# 10_RELAY.net
KiCad netlist of a schematic drawn in Altium Designer
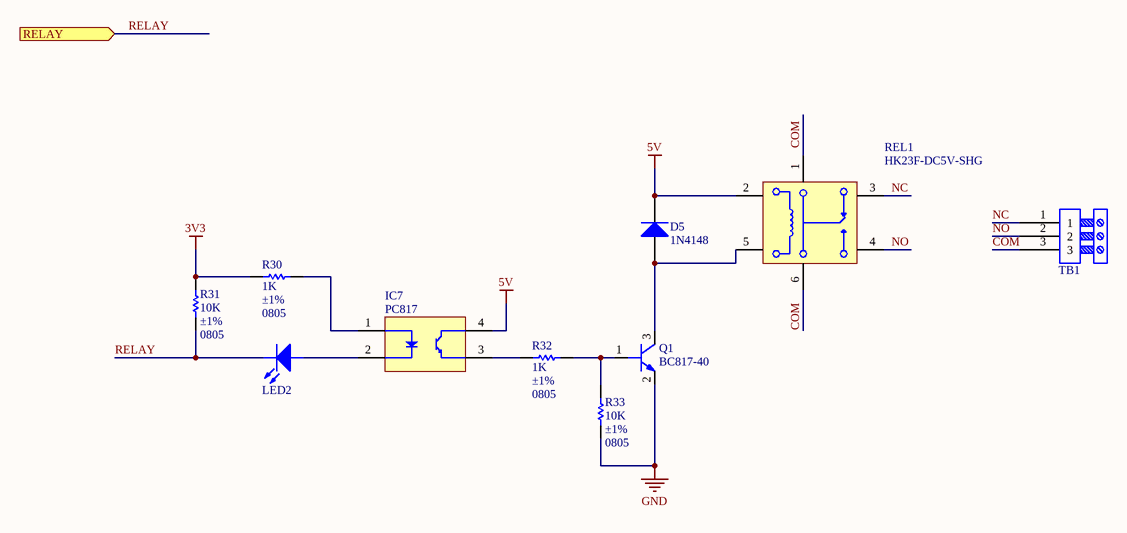
[diagram p0: 10.RELAY.SchDoc]

(export (version "E")
  (design (tool "Eeschema 10.0.6"))
  (components
    (comp (ref "D5")
      (value "1N4148")
      (footprint "SOD323")
      (description "DIODE GEN PURP 75V 150MA SOD323")
      (fields (field (name "PART NUMBER") "SSEM00021") (field (name "VOLTAGE") "75V"))
      (libsource (lib "ComponentDatabase") (part "DIODE"))
    )
    (comp (ref "IC7")
      (value "PC817")
      (footprint "SMD-4")
      (description "OPTOISOLTR 5KV TRANSISTOR 4-SMD")
      (fields
        (field (name "PART NUMBER") "SISO00004")
        (field (name "MANUFACTURER") "Everlight Electronics Co Ltd")
      )
      (libsource (lib "ComponentDatabase") (part "PC817"))
    )
    (comp (ref "LED2")
      (value "LED")
      (footprint "LEDC2012X70N_EIA0805_RED")
      (description "LED SUPER RED CLR THIN 0805 SMD")
      (fields (field (name "PART NUMBER") "SOPT00004") (field (name "MANUFACTURER") "Lite-On Inc"))
      (libsource (lib "ComponentDatabase") (part "LED"))
    )
    (comp (ref "Q1")
      (value "BC817-40")
      (footprint "SOT95P230X110-3N_SOT-23")
      (description "TRANS NPN 45V 0.5A SOT23")
      (fields (field (name "PART NUMBER") "STRANS00034") (field (name "MANUFACTURER") "NXP Semiconductors"))
      (libsource (lib "ComponentDatabase") (part "BC817"))
    )
    (comp (ref "R30")
      (value "1K")
      (footprint "RESC2013X65N_EIA0805")
      (description "RES SMD 1K OHM 1% 1/8W 0805")
      (fields
        (field (name "PART NUMBER") "SRES03010074")
        (field (name "TOLERANCE") "±1%")
        (field (name "PACKAGE / CASE") "0805")
        (field (name "MANUFACTURER") "Yageo")
      )
      (libsource (lib "ComponentDatabase") (part "RES"))
    )
    (comp (ref "R31")
      (value "10K")
      (footprint "RESC2013X65N_EIA0805")
      (description "RES SMD 10K OHM 1% 1/8W 0805")
      (fields
        (field (name "PART NUMBER") "SRES03010098")
        (field (name "TOLERANCE") "±1%")
        (field (name "PACKAGE / CASE") "0805")
        (field (name "MANUFACTURER") "Yageo")
      )
      (libsource (lib "ComponentDatabase") (part "RES"))
    )
    (comp (ref "R32")
      (value "1K")
      (footprint "RESC2013X65N_EIA0805")
      (description "RES SMD 1K OHM 1% 1/8W 0805")
      (fields
        (field (name "PART NUMBER") "SRES03010074")
        (field (name "TOLERANCE") "±1%")
        (field (name "PACKAGE / CASE") "0805")
        (field (name "MANUFACTURER") "Yageo")
      )
      (libsource (lib "ComponentDatabase") (part "RES"))
    )
    (comp (ref "R33")
      (value "10K")
      (footprint "RESC2013X65N_EIA0805")
      (description "RES SMD 10K OHM 1% 1/8W 0805")
      (fields
        (field (name "PART NUMBER") "SRES03010098")
        (field (name "TOLERANCE") "±1%")
        (field (name "PACKAGE / CASE") "0805")
        (field (name "MANUFACTURER") "Yageo")
      )
      (libsource (lib "ComponentDatabase") (part "RES"))
    )
    (comp (ref "REL1")
      (value "HK23F-DC5V-SHG")
      (footprint "HUIKE_HK23F-DC5V-SHG")
      (description "RELAY GEN PURPOSE SPDT 3A 5V")
      (fields (field (name "PART NUMBER") "SREL00004"))
      (libsource (lib "ComponentDatabase") (part "HK23F-DC5V-SHG"))
    )
    (comp (ref "TB1")
      (value "TB3_EURO")
      (footprint "TB3_EURO")
      (description "TERM BLOCK HDR 3POS VERT 3.81MM")
      (fields
        (field (name "PART NUMBER") "SCON00134")
        (field (name "MANUFACTURER") "On Shore Technology Inc.")
      )
      (libsource (lib "ComponentDatabase") (part "TB3_EURO"))
    )
  )
  (nets
    (net (code "1") (name "/COM") (class "Default")
      (node (ref "REL1") (pin "1") (pinfunction "1_1") (pintype "passive"))
      (node (ref "REL1") (pin "6") (pinfunction "6_6") (pintype "passive"))
      (node (ref "TB1") (pin "3") (pinfunction "3_3") (pintype "power_in"))
    )
    (net (code "2") (name "/NC") (class "Default")
      (node (ref "REL1") (pin "3") (pinfunction "3_3") (pintype "passive"))
      (node (ref "TB1") (pin "1") (pinfunction "1_1") (pintype "power_in"))
    )
    (net (code "3") (name "/NO") (class "Default")
      (node (ref "REL1") (pin "4") (pinfunction "4_4") (pintype "passive"))
      (node (ref "TB1") (pin "2") (pinfunction "2_2") (pintype "power_in"))
    )
    (net (code "4") (name "/RELAY") (class "Default")
      (node (ref "LED2") (pin "1") (pinfunction "1_1") (pintype "passive"))
      (node (ref "R31") (pin "2") (pinfunction "2_2") (pintype "passive"))
    )
    (net (code "5") (name "3V3") (class "Default")
      (node (ref "R30") (pin "1") (pinfunction "1_1") (pintype "passive"))
      (node (ref "R31") (pin "1") (pinfunction "1_1") (pintype "passive"))
    )
    (net (code "6") (name "5V") (class "Default")
      (node (ref "D5") (pin "1") (pinfunction "K_1") (pintype "passive"))
      (node (ref "IC7") (pin "4") (pinfunction "4_4") (pintype "passive"))
      (node (ref "REL1") (pin "2") (pinfunction "2_2") (pintype "passive"))
    )
    (net (code "7") (name "GND") (class "Default")
      (node (ref "Q1") (pin "2") (pinfunction "E_2") (pintype "passive"))
      (node (ref "R33") (pin "2") (pinfunction "2_2") (pintype "passive"))
    )
    (net (code "8") (name "Net-(D5-A)") (class "Default")
      (node (ref "D5") (pin "2") (pinfunction "A_2") (pintype "passive"))
      (node (ref "Q1") (pin "3") (pinfunction "C_3") (pintype "passive"))
      (node (ref "REL1") (pin "5") (pinfunction "5_5") (pintype "passive"))
    )
    (net (code "9") (name "Net-(IC7-Pad1)") (class "Default")
      (node (ref "IC7") (pin "1") (pinfunction "1_1") (pintype "passive"))
      (node (ref "R30") (pin "2") (pinfunction "2_2") (pintype "passive"))
    )
    (net (code "10") (name "Net-(IC7-Pad2)") (class "Default")
      (node (ref "IC7") (pin "2") (pinfunction "2_2") (pintype "passive"))
      (node (ref "LED2") (pin "2") (pinfunction "2_2") (pintype "passive"))
    )
    (net (code "11") (name "Net-(IC7-Pad3)") (class "Default")
      (node (ref "IC7") (pin "3") (pinfunction "3_3") (pintype "passive"))
      (node (ref "R32") (pin "2") (pinfunction "2_2") (pintype "passive"))
    )
    (net (code "12") (name "Net-(Q1-B)") (class "Default")
      (node (ref "Q1") (pin "1") (pinfunction "B_1") (pintype "passive"))
      (node (ref "R32") (pin "1") (pinfunction "1_1") (pintype "passive"))
      (node (ref "R33") (pin "1") (pinfunction "1_1") (pintype "passive"))
    )
  )
)
